# Pogo_Pin_Jig.net
KiCad netlist of a schematic drawn in EAGLE
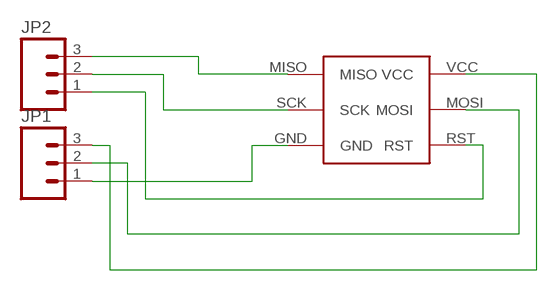
[diagram p0: schematic, sheet 1]

(export (version "E")
  (design (tool "Eeschema 10.0.6"))
  (components
    (comp (ref "JP1")
      (value "M03PTH")
      (footprint "eagle-import:1X03")
      (libsource (lib "eagle-import") (part "M03PTH"))
    )
    (comp (ref "JP2")
      (value "M03PTH")
      (footprint "eagle-import:1X03")
      (libsource (lib "eagle-import") (part "M03PTH"))
    )
    (comp (ref "U$1")
      (value "POGO_PIN_JIG_SPI")
      (footprint "eagle-import:POGO_PIN_JIG_SPI")
      (libsource (lib "eagle-import") (part "POGO_PIN_JIG_SPI"))
    )
  )
  (nets
    (net (code "1") (name "Net-(JP1-Pad1)") (class "Default")
      (node (ref "JP1") (pin "1") (pinfunction "1_1") (pintype "passive"))
      (node (ref "U$1") (pin "GND") (pinfunction "GND_GND") (pintype "bidirectional"))
    )
    (net (code "2") (name "Net-(JP1-Pad2)") (class "Default")
      (node (ref "JP1") (pin "2") (pinfunction "2_2") (pintype "passive"))
      (node (ref "U$1") (pin "MOSI") (pinfunction "MOSI_MOSI") (pintype "bidirectional"))
    )
    (net (code "3") (name "Net-(JP1-Pad3)") (class "Default")
      (node (ref "JP1") (pin "3") (pinfunction "3_3") (pintype "passive"))
      (node (ref "U$1") (pin "VCC") (pinfunction "VCC_VCC") (pintype "bidirectional"))
    )
    (net (code "4") (name "Net-(JP2-Pad1)") (class "Default")
      (node (ref "JP2") (pin "1") (pinfunction "1_1") (pintype "passive"))
      (node (ref "U$1") (pin "RST") (pinfunction "RST_RST") (pintype "bidirectional"))
    )
    (net (code "5") (name "Net-(JP2-Pad2)") (class "Default")
      (node (ref "JP2") (pin "2") (pinfunction "2_2") (pintype "passive"))
      (node (ref "U$1") (pin "SCK") (pinfunction "SCK_SCK") (pintype "bidirectional"))
    )
    (net (code "6") (name "Net-(JP2-Pad3)") (class "Default")
      (node (ref "JP2") (pin "3") (pinfunction "3_3") (pintype "passive"))
      (node (ref "U$1") (pin "MISO") (pinfunction "MISO_MISO") (pintype "bidirectional"))
    )
  )
)
